# ADE7756_board.net
KiCad netlist of a schematic drawn in EAGLE
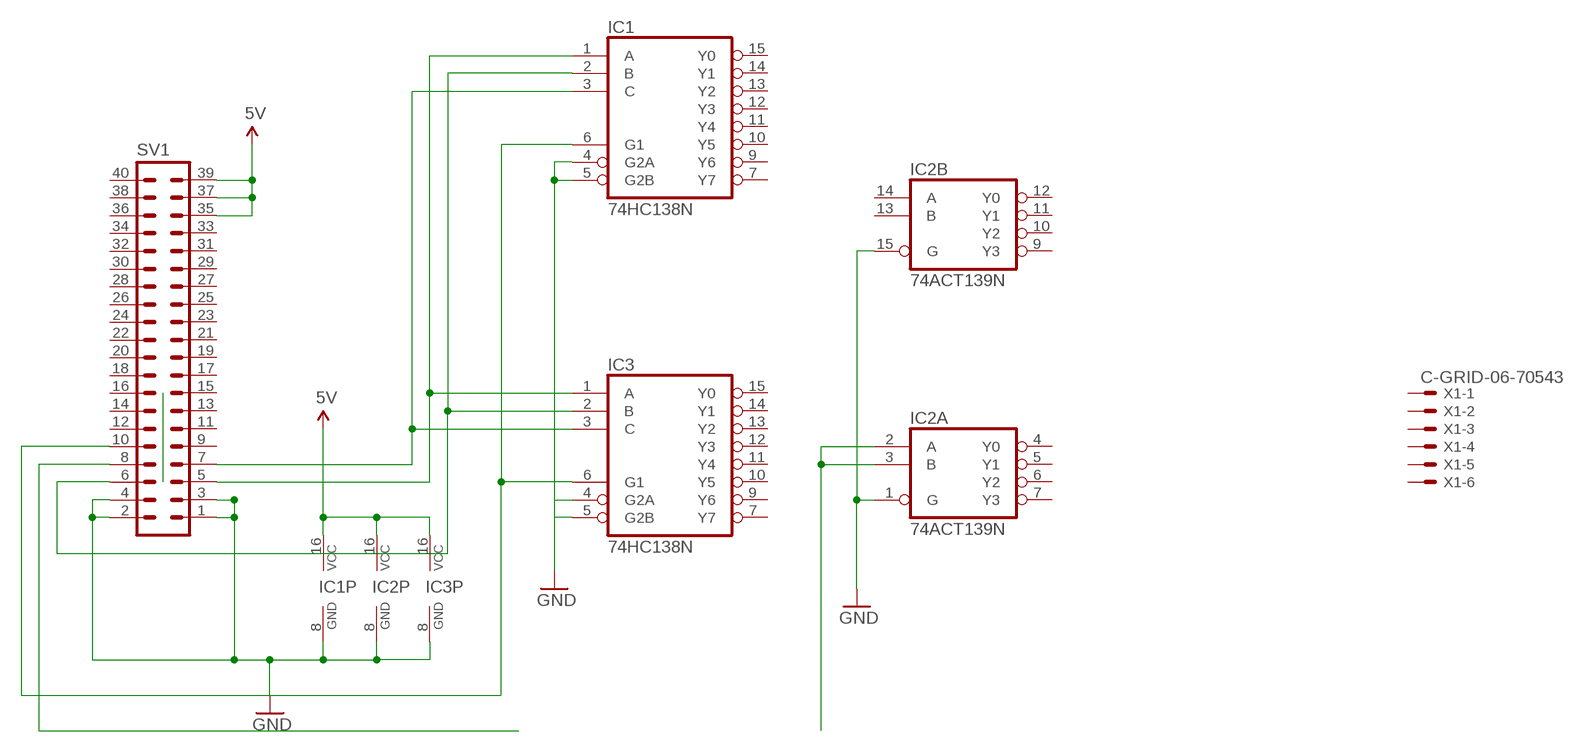
[diagram p0: schematic, sheet 1]

(export (version "E")
  (design (tool "Eeschema 10.0.6"))
  (components
    (comp (ref "IC1")
      (value "74HC138N")
      (footprint "eagle-import:DIL16")
      (libsource (lib "eagle-import") (part "74138NHC"))
    )
    (comp (ref "IC2")
      (value "74ACT139N")
      (footprint "eagle-import:DIL16")
      (libsource (lib "eagle-import") (part "74139NACT"))
    )
    (comp (ref "IC3")
      (value "74HC138N")
      (footprint "eagle-import:DIL16")
      (libsource (lib "eagle-import") (part "74138NHC"))
    )
    (comp (ref "SV1")
      (value "ML40")
      (footprint "eagle-import:ML40")
      (libsource (lib "eagle-import") (part "ML40"))
    )
    (comp (ref "X1")
      (value "C-GRID-06-70543")
      (footprint "eagle-import:70543-06")
      (libsource (lib "eagle-import") (part "C-GRID-06-70543"))
    )
  )
  (nets
    (net (code "1") (name "5V") (class "Default")
      (node (ref "IC1") (pin "16") (pinfunction "VCC_16") (pintype "power_in"))
      (node (ref "IC2") (pin "16") (pinfunction "VCC_16") (pintype "power_in"))
      (node (ref "IC3") (pin "16") (pinfunction "VCC_16") (pintype "power_in"))
      (node (ref "SV1") (pin "35") (pinfunction "35_35") (pintype "passive"))
      (node (ref "SV1") (pin "37") (pinfunction "37_37") (pintype "passive"))
      (node (ref "SV1") (pin "39") (pinfunction "39_39") (pintype "passive"))
    )
    (net (code "2") (name "GND") (class "Default")
      (node (ref "IC1") (pin "4") (pinfunction "G2A_4") (pintype "input"))
      (node (ref "IC1") (pin "5") (pinfunction "G2B_5") (pintype "input"))
      (node (ref "IC1") (pin "8") (pinfunction "GND_8") (pintype "power_in"))
      (node (ref "IC2") (pin "1") (pinfunction "G_1") (pintype "input"))
      (node (ref "IC2") (pin "15") (pinfunction "G_15") (pintype "input"))
      (node (ref "IC2") (pin "8") (pinfunction "GND_8") (pintype "power_in"))
      (node (ref "IC3") (pin "4") (pinfunction "G2A_4") (pintype "input"))
      (node (ref "IC3") (pin "5") (pinfunction "G2B_5") (pintype "input"))
      (node (ref "IC3") (pin "8") (pinfunction "GND_8") (pintype "power_in"))
      (node (ref "SV1") (pin "1") (pinfunction "1_1") (pintype "passive"))
      (node (ref "SV1") (pin "2") (pinfunction "2_2") (pintype "passive"))
      (node (ref "SV1") (pin "3") (pinfunction "3_3") (pintype "passive"))
      (node (ref "SV1") (pin "4") (pinfunction "4_4") (pintype "passive"))
    )
    (net (code "3") (name "Net-(IC1A-A)") (class "Default")
      (node (ref "IC1") (pin "1") (pinfunction "A_1") (pintype "input"))
      (node (ref "IC3") (pin "1") (pinfunction "A_1") (pintype "input"))
      (node (ref "SV1") (pin "5") (pinfunction "5_5") (pintype "passive"))
    )
    (net (code "4") (name "Net-(IC1A-B)") (class "Default")
      (node (ref "IC1") (pin "2") (pinfunction "B_2") (pintype "input"))
      (node (ref "IC3") (pin "2") (pinfunction "B_2") (pintype "input"))
      (node (ref "SV1") (pin "6") (pinfunction "6_6") (pintype "passive"))
    )
    (net (code "5") (name "Net-(IC1A-C)") (class "Default")
      (node (ref "IC1") (pin "3") (pinfunction "C_3") (pintype "input"))
      (node (ref "IC3") (pin "3") (pinfunction "C_3") (pintype "input"))
      (node (ref "SV1") (pin "7") (pinfunction "7_7") (pintype "passive"))
    )
    (net (code "6") (name "Net-(IC1A-G1)") (class "Default")
      (node (ref "IC1") (pin "6") (pinfunction "G1_6") (pintype "input"))
      (node (ref "IC3") (pin "6") (pinfunction "G1_6") (pintype "input"))
      (node (ref "SV1") (pin "10") (pinfunction "10_10") (pintype "passive"))
    )
    (net (code "7") (name "Net-(IC2A-A)") (class "Default")
      (node (ref "IC2") (pin "2") (pinfunction "A_2") (pintype "input"))
      (node (ref "IC2") (pin "3") (pinfunction "B_3") (pintype "input"))
    )
    (net (code "8") (name "unconnected-(IC1A-Y0-Pad15)") (class "Default")
      (node (ref "IC1") (pin "15") (pinfunction "Y0_15") (pintype "output"))
    )
    (net (code "9") (name "unconnected-(IC1A-Y1-Pad14)") (class "Default")
      (node (ref "IC1") (pin "14") (pinfunction "Y1_14") (pintype "output"))
    )
    (net (code "10") (name "unconnected-(IC1A-Y2-Pad13)") (class "Default")
      (node (ref "IC1") (pin "13") (pinfunction "Y2_13") (pintype "output"))
    )
    (net (code "11") (name "unconnected-(IC1A-Y3-Pad12)") (class "Default")
      (node (ref "IC1") (pin "12") (pinfunction "Y3_12") (pintype "output"))
    )
    (net (code "12") (name "unconnected-(IC1A-Y4-Pad11)") (class "Default")
      (node (ref "IC1") (pin "11") (pinfunction "Y4_11") (pintype "output"))
    )
    (net (code "13") (name "unconnected-(IC1A-Y5-Pad10)") (class "Default")
      (node (ref "IC1") (pin "10") (pinfunction "Y5_10") (pintype "output"))
    )
    (net (code "14") (name "unconnected-(IC1A-Y6-Pad9)") (class "Default")
      (node (ref "IC1") (pin "9") (pinfunction "Y6_9") (pintype "output"))
    )
    (net (code "15") (name "unconnected-(IC1A-Y7-Pad7)") (class "Default")
      (node (ref "IC1") (pin "7") (pinfunction "Y7_7") (pintype "output"))
    )
    (net (code "16") (name "unconnected-(IC2A-Y0-Pad4)") (class "Default")
      (node (ref "IC2") (pin "4") (pinfunction "Y0_4") (pintype "output"))
    )
    (net (code "17") (name "unconnected-(IC2A-Y1-Pad5)") (class "Default")
      (node (ref "IC2") (pin "5") (pinfunction "Y1_5") (pintype "output"))
    )
    (net (code "18") (name "unconnected-(IC2A-Y2-Pad6)") (class "Default")
      (node (ref "IC2") (pin "6") (pinfunction "Y2_6") (pintype "output"))
    )
    (net (code "19") (name "unconnected-(IC2A-Y3-Pad7)") (class "Default")
      (node (ref "IC2") (pin "7") (pinfunction "Y3_7") (pintype "output"))
    )
    (net (code "20") (name "unconnected-(IC2B-A-Pad14)") (class "Default")
      (node (ref "IC2") (pin "14") (pinfunction "A_14") (pintype "input"))
    )
    (net (code "21") (name "unconnected-(IC2B-B-Pad13)") (class "Default")
      (node (ref "IC2") (pin "13") (pinfunction "B_13") (pintype "input"))
    )
    (net (code "22") (name "unconnected-(IC2B-Y0-Pad12)") (class "Default")
      (node (ref "IC2") (pin "12") (pinfunction "Y0_12") (pintype "output"))
    )
    (net (code "23") (name "unconnected-(IC2B-Y1-Pad11)") (class "Default")
      (node (ref "IC2") (pin "11") (pinfunction "Y1_11") (pintype "output"))
    )
    (net (code "24") (name "unconnected-(IC2B-Y2-Pad10)") (class "Default")
      (node (ref "IC2") (pin "10") (pinfunction "Y2_10") (pintype "output"))
    )
    (net (code "25") (name "unconnected-(IC2B-Y3-Pad9)") (class "Default")
      (node (ref "IC2") (pin "9") (pinfunction "Y3_9") (pintype "output"))
    )
    (net (code "26") (name "unconnected-(IC3A-Y0-Pad15)") (class "Default")
      (node (ref "IC3") (pin "15") (pinfunction "Y0_15") (pintype "output"))
    )
    (net (code "27") (name "unconnected-(IC3A-Y1-Pad14)") (class "Default")
      (node (ref "IC3") (pin "14") (pinfunction "Y1_14") (pintype "output"))
    )
    (net (code "28") (name "unconnected-(IC3A-Y2-Pad13)") (class "Default")
      (node (ref "IC3") (pin "13") (pinfunction "Y2_13") (pintype "output"))
    )
    (net (code "29") (name "unconnected-(IC3A-Y3-Pad12)") (class "Default")
      (node (ref "IC3") (pin "12") (pinfunction "Y3_12") (pintype "output"))
    )
    (net (code "30") (name "unconnected-(IC3A-Y4-Pad11)") (class "Default")
      (node (ref "IC3") (pin "11") (pinfunction "Y4_11") (pintype "output"))
    )
    (net (code "31") (name "unconnected-(IC3A-Y5-Pad10)") (class "Default")
      (node (ref "IC3") (pin "10") (pinfunction "Y5_10") (pintype "output"))
    )
    (net (code "32") (name "unconnected-(IC3A-Y6-Pad9)") (class "Default")
      (node (ref "IC3") (pin "9") (pinfunction "Y6_9") (pintype "output"))
    )
    (net (code "33") (name "unconnected-(IC3A-Y7-Pad7)") (class "Default")
      (node (ref "IC3") (pin "7") (pinfunction "Y7_7") (pintype "output"))
    )
    (net (code "34") (name "unconnected-(SV1-Pad8)") (class "Default")
      (node (ref "SV1") (pin "8") (pinfunction "8_8") (pintype "passive"))
    )
    (net (code "35") (name "unconnected-(SV1-Pad9)") (class "Default")
      (node (ref "SV1") (pin "9") (pinfunction "9_9") (pintype "passive"))
    )
    (net (code "36") (name "unconnected-(SV1-Pad11)") (class "Default")
      (node (ref "SV1") (pin "11") (pinfunction "11_11") (pintype "passive"))
    )
    (net (code "37") (name "unconnected-(SV1-Pad12)") (class "Default")
      (node (ref "SV1") (pin "12") (pinfunction "12_12") (pintype "passive"))
    )
    (net (code "38") (name "unconnected-(SV1-Pad13)") (class "Default")
      (node (ref "SV1") (pin "13") (pinfunction "13_13") (pintype "passive"))
    )
    (net (code "39") (name "unconnected-(SV1-Pad14)") (class "Default")
      (node (ref "SV1") (pin "14") (pinfunction "14_14") (pintype "passive"))
    )
    (net (code "40") (name "unconnected-(SV1-Pad15)") (class "Default")
      (node (ref "SV1") (pin "15") (pinfunction "15_15") (pintype "passive"))
    )
    (net (code "41") (name "unconnected-(SV1-Pad16)") (class "Default")
      (node (ref "SV1") (pin "16") (pinfunction "16_16") (pintype "passive"))
    )
    (net (code "42") (name "unconnected-(SV1-Pad17)") (class "Default")
      (node (ref "SV1") (pin "17") (pinfunction "17_17") (pintype "passive"))
    )
    (net (code "43") (name "unconnected-(SV1-Pad18)") (class "Default")
      (node (ref "SV1") (pin "18") (pinfunction "18_18") (pintype "passive"))
    )
    (net (code "44") (name "unconnected-(SV1-Pad19)") (class "Default")
      (node (ref "SV1") (pin "19") (pinfunction "19_19") (pintype "passive"))
    )
    (net (code "45") (name "unconnected-(SV1-Pad20)") (class "Default")
      (node (ref "SV1") (pin "20") (pinfunction "20_20") (pintype "passive"))
    )
    (net (code "46") (name "unconnected-(SV1-Pad21)") (class "Default")
      (node (ref "SV1") (pin "21") (pinfunction "21_21") (pintype "passive"))
    )
    (net (code "47") (name "unconnected-(SV1-Pad22)") (class "Default")
      (node (ref "SV1") (pin "22") (pinfunction "22_22") (pintype "passive"))
    )
    (net (code "48") (name "unconnected-(SV1-Pad23)") (class "Default")
      (node (ref "SV1") (pin "23") (pinfunction "23_23") (pintype "passive"))
    )
    (net (code "49") (name "unconnected-(SV1-Pad24)") (class "Default")
      (node (ref "SV1") (pin "24") (pinfunction "24_24") (pintype "passive"))
    )
    (net (code "50") (name "unconnected-(SV1-Pad25)") (class "Default")
      (node (ref "SV1") (pin "25") (pinfunction "25_25") (pintype "passive"))
    )
    (net (code "51") (name "unconnected-(SV1-Pad26)") (class "Default")
      (node (ref "SV1") (pin "26") (pinfunction "26_26") (pintype "passive"))
    )
    (net (code "52") (name "unconnected-(SV1-Pad27)") (class "Default")
      (node (ref "SV1") (pin "27") (pinfunction "27_27") (pintype "passive"))
    )
    (net (code "53") (name "unconnected-(SV1-Pad28)") (class "Default")
      (node (ref "SV1") (pin "28") (pinfunction "28_28") (pintype "passive"))
    )
    (net (code "54") (name "unconnected-(SV1-Pad29)") (class "Default")
      (node (ref "SV1") (pin "29") (pinfunction "29_29") (pintype "passive"))
    )
    (net (code "55") (name "unconnected-(SV1-Pad30)") (class "Default")
      (node (ref "SV1") (pin "30") (pinfunction "30_30") (pintype "passive"))
    )
    (net (code "56") (name "unconnected-(SV1-Pad31)") (class "Default")
      (node (ref "SV1") (pin "31") (pinfunction "31_31") (pintype "passive"))
    )
    (net (code "57") (name "unconnected-(SV1-Pad32)") (class "Default")
      (node (ref "SV1") (pin "32") (pinfunction "32_32") (pintype "passive"))
    )
    (net (code "58") (name "unconnected-(SV1-Pad33)") (class "Default")
      (node (ref "SV1") (pin "33") (pinfunction "33_33") (pintype "passive"))
    )
    (net (code "59") (name "unconnected-(SV1-Pad34)") (class "Default")
      (node (ref "SV1") (pin "34") (pinfunction "34_34") (pintype "passive"))
    )
    (net (code "60") (name "unconnected-(SV1-Pad36)") (class "Default")
      (node (ref "SV1") (pin "36") (pinfunction "36_36") (pintype "passive"))
    )
    (net (code "61") (name "unconnected-(SV1-Pad38)") (class "Default")
      (node (ref "SV1") (pin "38") (pinfunction "38_38") (pintype "passive"))
    )
    (net (code "62") (name "unconnected-(SV1-Pad40)") (class "Default")
      (node (ref "SV1") (pin "40") (pinfunction "40_40") (pintype "passive"))
    )
    (net (code "63") (name "unconnected-(X1A-S-Pad1)") (class "Default")
      (node (ref "X1") (pin "1") (pinfunction "S_1") (pintype "passive"))
    )
    (net (code "64") (name "unconnected-(X1B-S-Pad2)") (class "Default")
      (node (ref "X1") (pin "2") (pinfunction "S_2") (pintype "passive"))
    )
    (net (code "65") (name "unconnected-(X1C-S-Pad3)") (class "Default")
      (node (ref "X1") (pin "3") (pinfunction "S_3") (pintype "passive"))
    )
    (net (code "66") (name "unconnected-(X1D-S-Pad4)") (class "Default")
      (node (ref "X1") (pin "4") (pinfunction "S_4") (pintype "passive"))
    )
    (net (code "67") (name "unconnected-(X1E-S-Pad5)") (class "Default")
      (node (ref "X1") (pin "5") (pinfunction "S_5") (pintype "passive"))
    )
    (net (code "68") (name "unconnected-(X1F-S-Pad6)") (class "Default")
      (node (ref "X1") (pin "6") (pinfunction "S_6") (pintype "passive"))
    )
  )
)
